# PCI_Express.net
KiCad netlist of a schematic drawn in Altium Designer
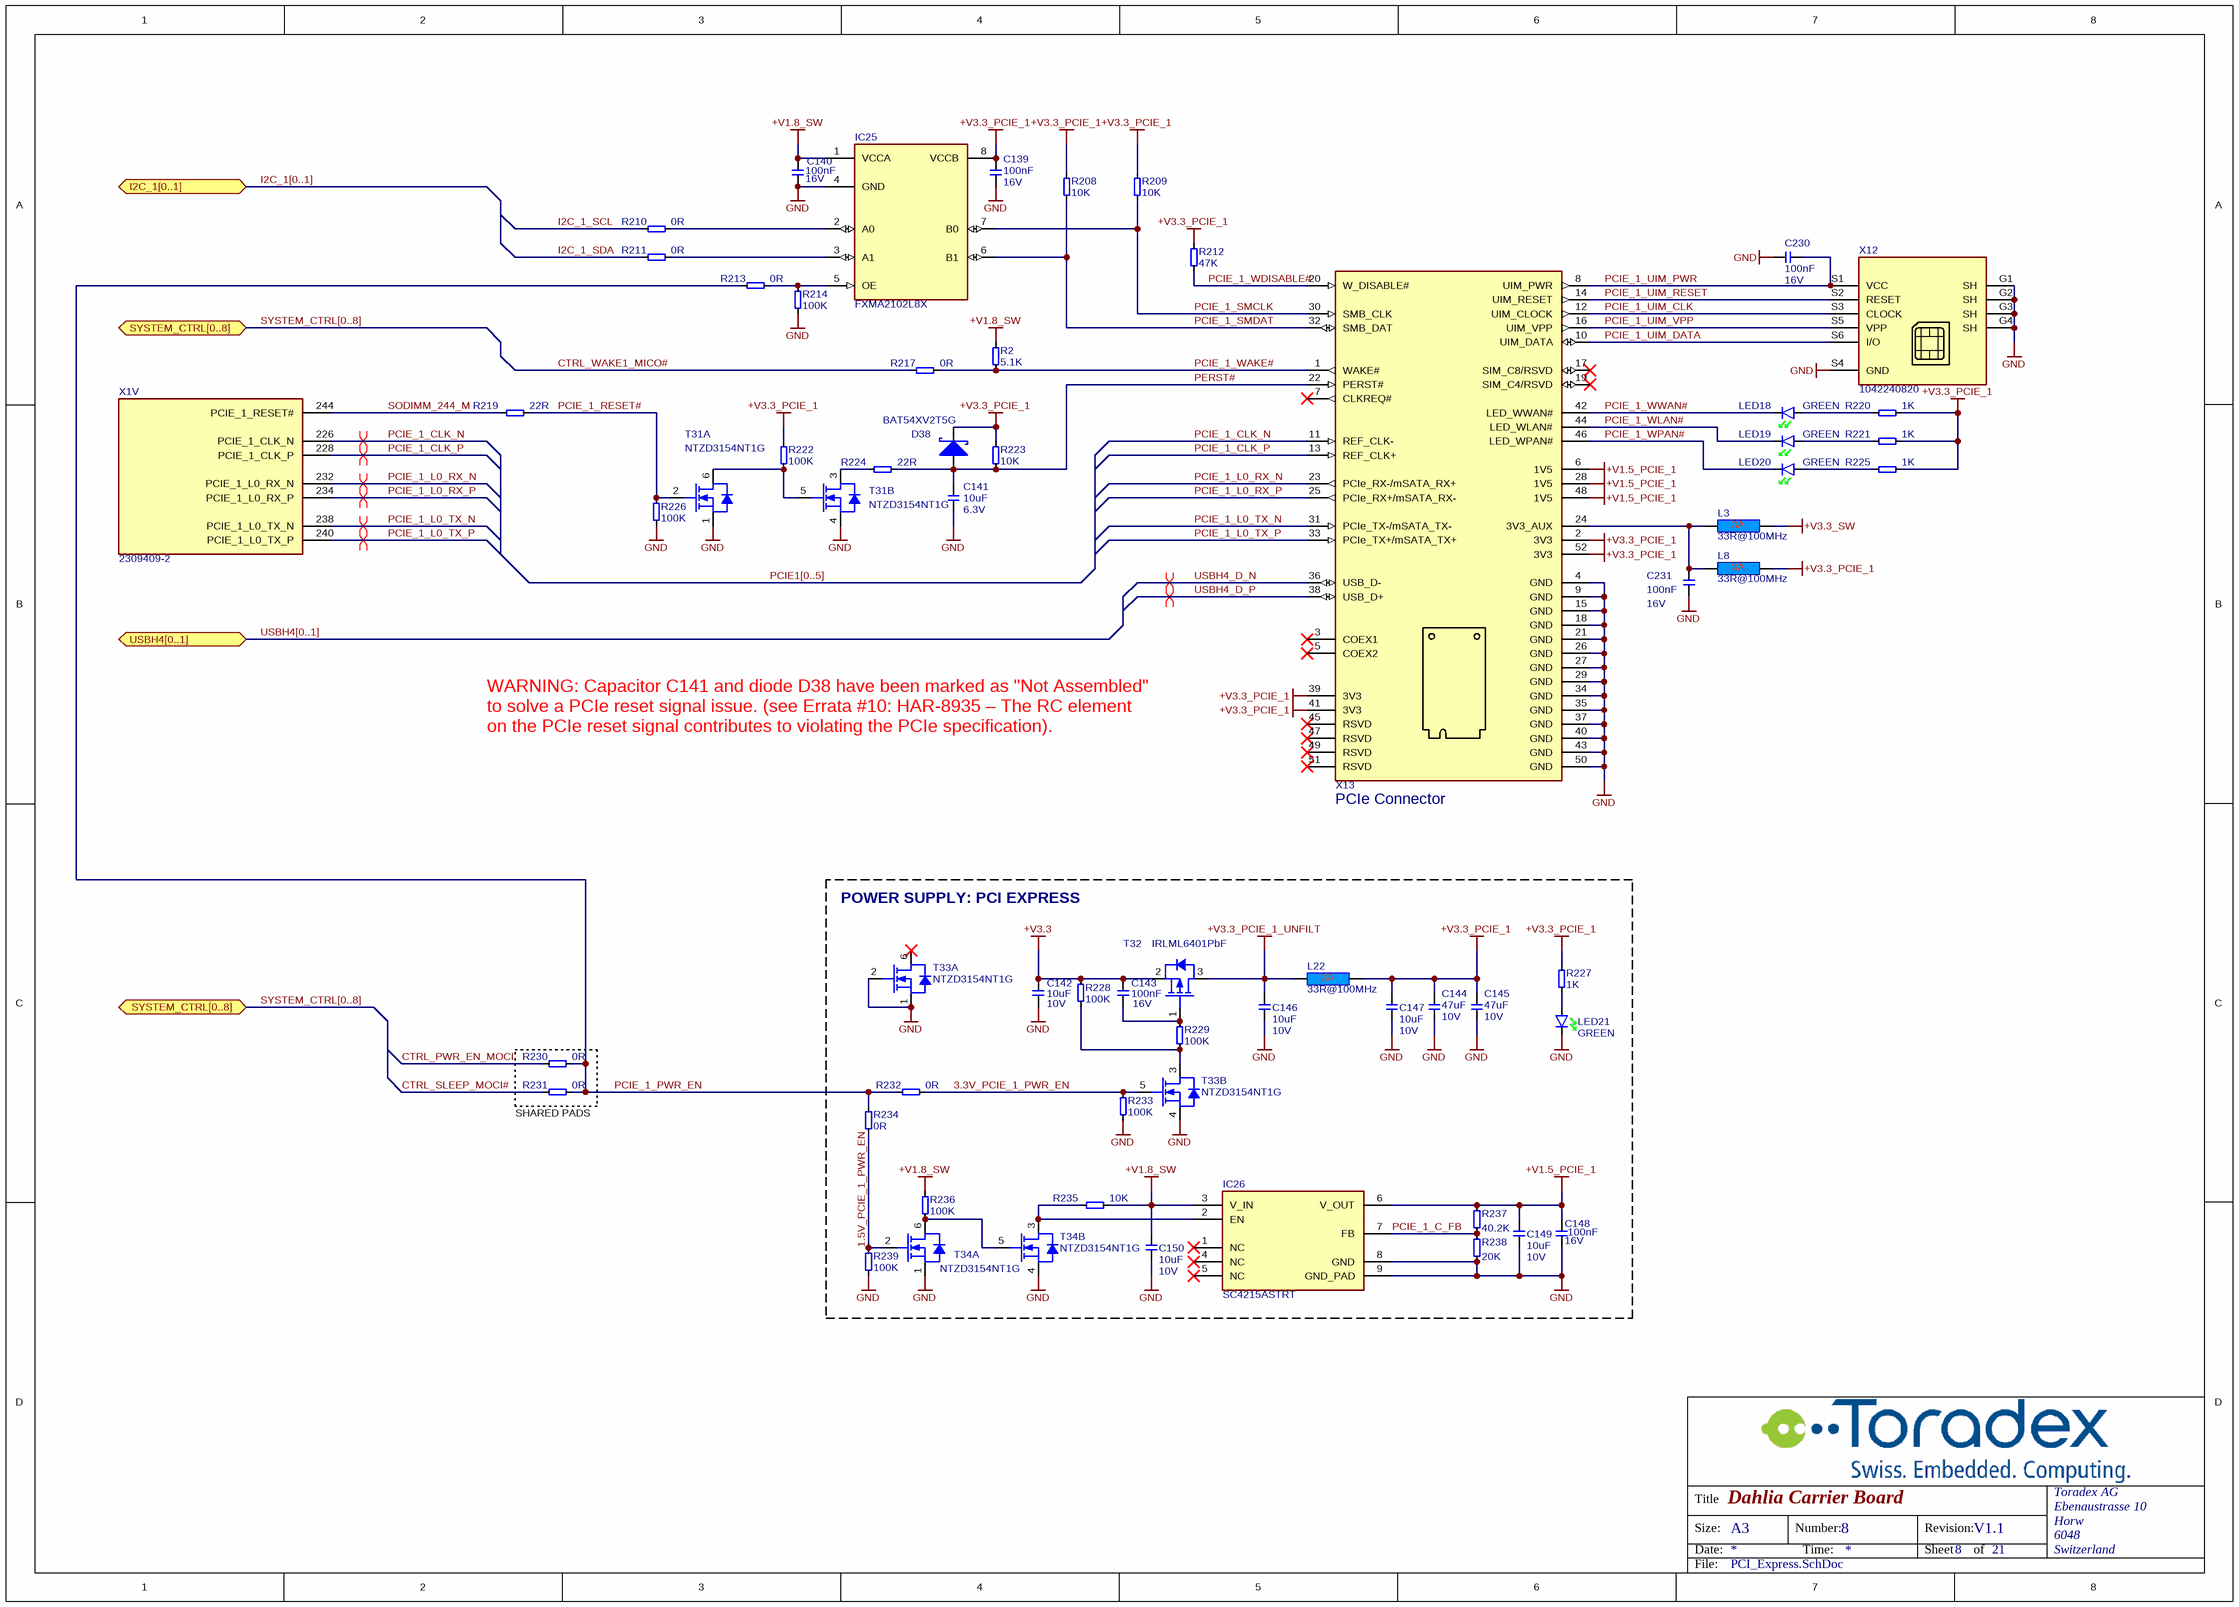
[diagram p0: PCI_Express.SchDoc]

(export (version "E")
  (design (tool "Eeschema 10.0.6"))
  (components
    (comp (ref "C139")
      (value "100nF")
      (footprint "CAPC1005X60N")
      (description "Capacitor Ceramic X7R 100nF 16V 10% 0402")
      (fields (field (name "TOLERANCE") "10%") (field (name "RATING") "16V"))
      (libsource (lib "Dahlia Carrier Board") (part "C-X7R-100nF-16V-10%-0402"))
    )
    (comp (ref "C140")
      (value "100nF")
      (footprint "CAPC1005X60N")
      (description "Capacitor Ceramic X7R 100nF 16V 10% 0402")
      (fields (field (name "TOLERANCE") "10%") (field (name "RATING") "16V"))
      (libsource (lib "Dahlia Carrier Board") (part "C-X7R-100nF-16V-10%-0402"))
    )
    (comp (ref "C141")
      (value "10uF")
      (footprint "CAPC1005X60N")
      (description "Capacitor Ceramic X5R 10uF 6.3V 20% 0402")
      (fields (field (name "TOLERANCE") "20%") (field (name "RATING") "6.3V"))
      (libsource (lib "Dahlia Carrier Board") (part "C-X5R-10u-6.3V-20%-0402"))
    )
    (comp (ref "C142")
      (value "10uF")
      (footprint "T_CAPC0603X33N")
      (description "Capacitor Ceramic X5R 10uF 10V 20% 0603")
      (fields (field (name "TOLERANCE") "20%") (field (name "RATING") "10V"))
      (libsource (lib "Dahlia Carrier Board") (part "C-X5R-10uF-10V-20%-0603"))
    )
    (comp (ref "C143")
      (value "100nF")
      (footprint "CAPC1005X60N")
      (description "Capacitor Ceramic X7R 100nF 16V 10% 0402")
      (fields (field (name "TOLERANCE") "10%") (field (name "RATING") "16V"))
      (libsource (lib "Dahlia Carrier Board") (part "C-X7R-100nF-16V-10%-0402"))
    )
    (comp (ref "C144")
      (value "47uF")
      (footprint "T_CAPC0805X125N")
      (description "Capacitor Ceramic X5R 47uF 10V 20% 0805")
      (fields (field (name "TOLERANCE") "20%") (field (name "RATING") "10V"))
      (libsource (lib "Dahlia Carrier Board") (part "C-X5R-47uF-10V-20%-0805"))
    )
    (comp (ref "C145")
      (value "47uF")
      (footprint "T_CAPC0805X125N")
      (description "Capacitor Ceramic X5R 47uF 10V 20% 0805")
      (fields (field (name "TOLERANCE") "20%") (field (name "RATING") "10V"))
      (libsource (lib "Dahlia Carrier Board") (part "C-X5R-47uF-10V-20%-0805"))
    )
    (comp (ref "C146")
      (value "10uF")
      (footprint "T_CAPC0603X33N")
      (description "Capacitor Ceramic X5R 10uF 10V 20% 0603")
      (fields (field (name "TOLERANCE") "20%") (field (name "RATING") "10V"))
      (libsource (lib "Dahlia Carrier Board") (part "C-X5R-10uF-10V-20%-0603"))
    )
    (comp (ref "C147")
      (value "10uF")
      (footprint "T_CAPC0603X33N")
      (description "Capacitor Ceramic X5R 10uF 10V 20% 0603")
      (fields (field (name "TOLERANCE") "20%") (field (name "RATING") "10V"))
      (libsource (lib "Dahlia Carrier Board") (part "C-X5R-10uF-10V-20%-0603"))
    )
    (comp (ref "C148")
      (value "100nF")
      (footprint "CAPC1005X60N")
      (description "Capacitor Ceramic X7R 100nF 16V 10% 0402")
      (fields (field (name "TOLERANCE") "10%") (field (name "RATING") "16V"))
      (libsource (lib "Dahlia Carrier Board") (part "C-X7R-100nF-16V-10%-0402"))
    )
    (comp (ref "C149")
      (value "10uF")
      (footprint "T_CAPC0603X33N")
      (description "Capacitor Ceramic X5R 10uF 10V 20% 0603")
      (fields (field (name "TOLERANCE") "20%") (field (name "RATING") "10V"))
      (libsource (lib "Dahlia Carrier Board") (part "C-X5R-10uF-10V-20%-0603"))
    )
    (comp (ref "C150")
      (value "10uF")
      (footprint "T_CAPC0603X33N")
      (description "Capacitor Ceramic X5R 10uF 10V 20% 0603")
      (fields (field (name "TOLERANCE") "20%") (field (name "RATING") "10V"))
      (libsource (lib "Dahlia Carrier Board") (part "C-X5R-10uF-10V-20%-0603"))
    )
    (comp (ref "C230")
      (value "100nF")
      (footprint "CAPC1005X60N")
      (description "Capacitor Ceramic X7R 100nF 16V 10% 0402")
      (fields (field (name "TOLERANCE") "10%") (field (name "RATING") "16V"))
      (libsource (lib "Dahlia Carrier Board") (part "C-X7R-100nF-16V-10%-0402"))
    )
    (comp (ref "C231")
      (value "100nF")
      (footprint "CAPC1005X60N")
      (description "Capacitor Ceramic X7R 100nF 16V 10% 0402")
      (fields (field (name "TOLERANCE") "10%") (field (name "RATING") "16V"))
      (libsource (lib "Dahlia Carrier Board") (part "C-X7R-100nF-16V-10%-0402"))
    )
    (comp (ref "D38")
      (value "BAT54XV2T5G")
      (footprint "SOD-523")
      (description "Schottky Barrier Rectifier")
      (fields (field (name "MANUFACTURER PART NO.") "BAT54XV2T5G"))
      (libsource (lib "Dahlia Carrier Board") (part "D-BAT54-SOD523"))
    )
    (comp (ref "IC25")
      (value "FXMA2102L8X")
      (footprint "IC-MicroPak50P160X2160X55-8N")
      (description "Voltage Level Translator for I2C Applications")
      (fields (field (name "MANUFACTURER PART NO.") "FXMA2102L8X"))
      (libsource (lib "Dahlia Carrier Board") (part "IC-ONsemi-FXMA2102L8X"))
    )
    (comp (ref "IC26")
      (value "IC-Semtech-SC4215A")
      (footprint "IC-SOIC127P650X175_HS-8N")
      (description "LDO TO 2A")
      (fields (field (name "MANUFACTURER PART NO.") "SC4215ASTRT"))
      (libsource (lib "Dahlia Carrier Board") (part "IC-Semtech-SC4215A"))
    )
    (comp (ref "L3")
      (value "33R@100MHz")
      (footprint "INDC1608X95N")
      (description "33R@100MHz 3A EMI FILTER")
      (fields (field (name "TOLERANCE") "25%"))
      (libsource (lib "Dahlia Carrier Board") (part "L-33R@100MHz-3A-25%-0603"))
    )
    (comp (ref "L8")
      (value "33R@100MHz")
      (footprint "INDC1608X95N")
      (description "33R@100MHz 3A EMI FILTER")
      (fields (field (name "TOLERANCE") "25%"))
      (libsource (lib "Dahlia Carrier Board") (part "L-33R@100MHz-3A-25%-0603"))
    )
    (comp (ref "L22")
      (value "33R@100MHz")
      (footprint "INDC1608X95N")
      (description "33R@100MHz 3A EMI FILTER")
      (fields (field (name "TOLERANCE") "25%"))
      (libsource (lib "Dahlia Carrier Board") (part "L-33R@100MHz-3A-25%-0603"))
    )
    (comp (ref "LED18")
      (value "LTST-C190GKT")
      (footprint "T_Liteon_LTST-C190GKT")
      (description "LED green Lite-ON LTST-C190GKT")
      (fields (field (name "COLOR") "GREEN"))
      (libsource (lib "Dahlia Carrier Board") (part "LED-LiteOn-LTST-C190GKT"))
    )
    (comp (ref "LED19")
      (value "LTST-C190GKT")
      (footprint "T_Liteon_LTST-C190GKT")
      (description "LED green Lite-ON LTST-C190GKT")
      (fields (field (name "COLOR") "GREEN"))
      (libsource (lib "Dahlia Carrier Board") (part "LED-LiteOn-LTST-C190GKT"))
    )
    (comp (ref "LED20")
      (value "LTST-C190GKT")
      (footprint "T_Liteon_LTST-C190GKT")
      (description "LED green Lite-ON LTST-C190GKT")
      (fields (field (name "COLOR") "GREEN"))
      (libsource (lib "Dahlia Carrier Board") (part "LED-LiteOn-LTST-C190GKT"))
    )
    (comp (ref "LED21")
      (value "LTST-C190GKT")
      (footprint "T_Liteon_LTST-C190GKT")
      (description "LED green Lite-ON LTST-C190GKT")
      (fields (field (name "COLOR") "GREEN"))
      (libsource (lib "Dahlia Carrier Board") (part "LED-LiteOn-LTST-C190GKT"))
    )
    (comp (ref "R2")
      (value "5.1K")
      (footprint "T_RESC0603X30N")
      (description "Resistor 5.1 Kohm 63mW 1% 0603")
      (fields (field (name "TOLERANCE") "1%"))
      (libsource (lib "Dahlia Carrier Board") (part "R-5.1K-63mW-1%-0603"))
    )
    (comp (ref "R208")
      (value "10K")
      (footprint "RESC1005X40N")
      (description "Resistor 10 Kohm 63mW 5% 0402")
      (fields (field (name "TOLERANCE") "5%"))
      (libsource (lib "Dahlia Carrier Board") (part "R-10K-63mW-5%-0402"))
    )
    (comp (ref "R209")
      (value "10K")
      (footprint "RESC1005X40N")
      (description "Resistor 10 Kohm 63mW 5% 0402")
      (fields (field (name "TOLERANCE") "5%"))
      (libsource (lib "Dahlia Carrier Board") (part "R-10K-63mW-5%-0402"))
    )
    (comp (ref "R210")
      (value "0R")
      (footprint "T_RESC0603X30N")
      (description "Resistor 0 ohm 63mW 1% 0603")
      (fields (field (name "TOLERANCE") "1%"))
      (libsource (lib "Dahlia Carrier Board") (part "R-0R-63mW-1%-0603"))
    )
    (comp (ref "R211")
      (value "0R")
      (footprint "T_RESC0603X30N")
      (description "Resistor 0 ohm 63mW 1% 0603")
      (fields (field (name "TOLERANCE") "1%"))
      (libsource (lib "Dahlia Carrier Board") (part "R-0R-63mW-1%-0603"))
    )
    (comp (ref "R212")
      (value "47K")
      (footprint "RESC1005X40N")
      (description "Resistor 47 Kohm 63mW 1% 0402")
      (fields (field (name "TOLERANCE") "1%"))
      (libsource (lib "Dahlia Carrier Board") (part "R-47K-63mW-1%-0402"))
    )
    (comp (ref "R213")
      (value "0R")
      (footprint "T_RESC0603X30N")
      (description "Resistor 0 ohm 63mW 1% 0603")
      (fields (field (name "TOLERANCE") "1%"))
      (libsource (lib "Dahlia Carrier Board") (part "R-0R-63mW-1%-0603"))
    )
    (comp (ref "R214")
      (value "100K")
      (footprint "RESC1005X40N")
      (description "Resistor 100 Kohm 63mW 5% 0402")
      (fields (field (name "TOLERANCE") "5%"))
      (libsource (lib "Dahlia Carrier Board") (part "R-100K-63mW-5%-0402"))
    )
    (comp (ref "R217")
      (value "0R")
      (footprint "T_RESC0603X30N")
      (description "Resistor 0 ohm 63mW 1% 0603")
      (fields (field (name "TOLERANCE") "1%"))
      (libsource (lib "Dahlia Carrier Board") (part "R-0R-63mW-1%-0603"))
    )
    (comp (ref "R219")
      (value "22R")
      (footprint "RESC1005X40N")
      (description "Resistor 22 ohm 63mW 5% 0402")
      (fields (field (name "TOLERANCE") "5%"))
      (libsource (lib "Dahlia Carrier Board") (part "R-22R-63mW-5%-0402"))
    )
    (comp (ref "R220")
      (value "1K")
      (footprint "RESC1005X40N")
      (description "Resistor 1 Kohm 63mW 5% 0402")
      (fields (field (name "TOLERANCE") "5%"))
      (libsource (lib "Dahlia Carrier Board") (part "R-1K-63mW-5%-0402"))
    )
    (comp (ref "R221")
      (value "1K")
      (footprint "RESC1005X40N")
      (description "Resistor 1 Kohm 63mW 5% 0402")
      (fields (field (name "TOLERANCE") "5%"))
      (libsource (lib "Dahlia Carrier Board") (part "R-1K-63mW-5%-0402"))
    )
    (comp (ref "R222")
      (value "100K")
      (footprint "RESC1005X40N")
      (description "Resistor 100 Kohm 63mW 5% 0402")
      (fields (field (name "TOLERANCE") "5%"))
      (libsource (lib "Dahlia Carrier Board") (part "R-100K-63mW-5%-0402"))
    )
    (comp (ref "R223")
      (value "10K")
      (footprint "RESC1005X40N")
      (description "Resistor 10 Kohm 63mW 5% 0402")
      (fields (field (name "TOLERANCE") "5%"))
      (libsource (lib "Dahlia Carrier Board") (part "R-10K-63mW-5%-0402"))
    )
    (comp (ref "R224")
      (value "22R")
      (footprint "RESC1005X40N")
      (description "Resistor 22 ohm 63mW 5% 0402")
      (fields (field (name "TOLERANCE") "5%"))
      (libsource (lib "Dahlia Carrier Board") (part "R-22R-63mW-5%-0402"))
    )
    (comp (ref "R225")
      (value "1K")
      (footprint "RESC1005X40N")
      (description "Resistor 1 Kohm 63mW 5% 0402")
      (fields (field (name "TOLERANCE") "5%"))
      (libsource (lib "Dahlia Carrier Board") (part "R-1K-63mW-5%-0402"))
    )
    (comp (ref "R226")
      (value "100K")
      (footprint "RESC1005X40N")
      (description "Resistor 100 Kohm 63mW 5% 0402")
      (fields (field (name "TOLERANCE") "5%"))
      (libsource (lib "Dahlia Carrier Board") (part "R-100K-63mW-5%-0402"))
    )
    (comp (ref "R227")
      (value "1K")
      (footprint "RESC1005X40N")
      (description "Resistor 1 Kohm 63mW 5% 0402")
      (fields (field (name "TOLERANCE") "5%"))
      (libsource (lib "Dahlia Carrier Board") (part "R-1K-63mW-5%-0402"))
    )
    (comp (ref "R228")
      (value "100K")
      (footprint "RESC1005X40N")
      (description "Resistor 100 Kohm 63mW 5% 0402")
      (fields (field (name "TOLERANCE") "5%"))
      (libsource (lib "Dahlia Carrier Board") (part "R-100K-63mW-5%-0402"))
    )
    (comp (ref "R229")
      (value "100K")
      (footprint "RESC1005X40N")
      (description "Resistor 100 Kohm 63mW 5% 0402")
      (fields (field (name "TOLERANCE") "5%"))
      (libsource (lib "Dahlia Carrier Board") (part "R-100K-63mW-5%-0402"))
    )
    (comp (ref "R230")
      (value "0R")
      (footprint "T_RESC0603X30N")
      (description "Resistor 0 ohm 63mW 1% 0603")
      (fields (field (name "TOLERANCE") "1%"))
      (libsource (lib "Dahlia Carrier Board") (part "R-0R-63mW-1%-0603"))
    )
    (comp (ref "R231")
      (value "0R")
      (footprint "T_RESC0603X30N")
      (description "Resistor 0 ohm 63mW 1% 0603")
      (fields (field (name "TOLERANCE") "1%"))
      (libsource (lib "Dahlia Carrier Board") (part "R-0R-63mW-1%-0603"))
    )
    (comp (ref "R232")
      (value "0R")
      (footprint "T_RESC0603X30N")
      (description "Resistor 0 ohm 63mW 1% 0603")
      (fields (field (name "TOLERANCE") "1%"))
      (libsource (lib "Dahlia Carrier Board") (part "R-0R-63mW-1%-0603"))
    )
    (comp (ref "R233")
      (value "100K")
      (footprint "RESC1005X40N")
      (description "Resistor 100 Kohm 63mW 5% 0402")
      (fields (field (name "TOLERANCE") "5%"))
      (libsource (lib "Dahlia Carrier Board") (part "R-100K-63mW-5%-0402"))
    )
    (comp (ref "R234")
      (value "0R")
      (footprint "T_RESC0603X30N")
      (description "Resistor 0 ohm 63mW 1% 0603")
      (fields (field (name "TOLERANCE") "1%"))
      (libsource (lib "Dahlia Carrier Board") (part "R-0R-63mW-1%-0603"))
    )
    (comp (ref "R235")
      (value "10K")
      (footprint "RESC1005X40N")
      (description "Resistor 10 Kohm 63mW 5% 0402")
      (fields (field (name "TOLERANCE") "5%"))
      (libsource (lib "Dahlia Carrier Board") (part "R-10K-63mW-5%-0402"))
    )
    (comp (ref "R236")
      (value "100K")
      (footprint "RESC1005X40N")
      (description "Resistor 100 Kohm 63mW 5% 0402")
      (fields (field (name "TOLERANCE") "5%"))
      (libsource (lib "Dahlia Carrier Board") (part "R-100K-63mW-5%-0402"))
    )
    (comp (ref "R237")
      (value "40.2K")
      (footprint "RESC1005X40N")
      (description "Resistor 40.2 Kohm 63mW 1% 0402")
      (fields (field (name "TOLERANCE") "1%"))
      (libsource (lib "Dahlia Carrier Board") (part "R-40.2KR-63mW-1%-0402"))
    )
    (comp (ref "R238")
      (value "20K")
      (footprint "RESC1005X40N")
      (description "Resistor 20 Kohm 63mW 1% 0402")
      (fields (field (name "TOLERANCE") "1%"))
      (libsource (lib "Dahlia Carrier Board") (part "R-20KR-63mW-1%-0402"))
    )
    (comp (ref "R239")
      (value "100K")
      (footprint "RESC1005X40N")
      (description "Resistor 100 Kohm 63mW 5% 0402")
      (fields (field (name "TOLERANCE") "5%"))
      (libsource (lib "Dahlia Carrier Board") (part "R-100K-63mW-5%-0402"))
    )
    (comp (ref "T31")
      (value "T-ONSemi-NTZD3154NT1G")
      (footprint "SOTFL50P160X60-6N")
      (description "Dual N-Channel 20V (D-S)  MOSFET")
      (fields (field (name "MANUFACTURER PART NO.") "NTZD3154NT1G"))
      (libsource (lib "Dahlia Carrier Board") (part "T-ONSemi-NTZD3154NT1G"))
    )
    (comp (ref "T32")
      (value "IRLML6401PbF")
      (footprint "SOT95P237X112-3N")
      (description "p-channel MOSFET, IRLML6401PbF")
      (libsource (lib "Dahlia Carrier Board") (part "T-IR-IRLML6401PbF-SOT-23"))
    )
    (comp (ref "T33")
      (value "T-ONSemi-NTZD3154NT1G")
      (footprint "SOTFL50P160X60-6N")
      (description "Dual N-Channel 20V (D-S)  MOSFET")
      (fields (field (name "MANUFACTURER PART NO.") "NTZD3154NT1G"))
      (libsource (lib "Dahlia Carrier Board") (part "T-ONSemi-NTZD3154NT1G"))
    )
    (comp (ref "T34")
      (value "T-ONSemi-NTZD3154NT1G")
      (footprint "SOTFL50P160X60-6N")
      (description "Dual N-Channel 20V (D-S)  MOSFET")
      (fields (field (name "MANUFACTURER PART NO.") "NTZD3154NT1G"))
      (libsource (lib "Dahlia Carrier Board") (part "T-ONSemi-NTZD3154NT1G"))
    )
    (comp (ref "X1")
      (value "2309409-2")
      (footprint "CON-TE-2309409-2-SOLDERABLE-STANDOFFS")
      (description "DDR4 SODIMM Socket, 260 pins, 5.2mm(H), 0.5mm Pitch")
      (libsource (lib "Dahlia Carrier Board") (part "CON-TE-2309409-2"))
    )
    (comp (ref "X12")
      (value "1042240820")
      (footprint "T_Molex_1042240820")
      (description "6 Contacts Nano Sim Card Holder")
      (fields (field (name "MANUFACTURER PART NO.") "1042240820"))
      (libsource (lib "Dahlia Carrier Board") (part "CON-Molex-1042240820"))
    )
    (comp (ref "X13")
      (value "67910-5700")
      (footprint "CON-Molex-67910-5700-Half/Full")
      (description "PCIe_Mini Card Holder")
      (libsource (lib "Dahlia Carrier Board") (part "CON-Molex-67910-5700"))
    )
  )
  (nets
    (net (code "20") (name "+V1.5_PCIE_1") (class "Default")
      (node (ref "C148") (pin "2") (pinfunction "2_2") (pintype "passive"))
      (node (ref "C149") (pin "2") (pinfunction "2_2") (pintype "passive"))
      (node (ref "IC26") (pin "6") (pinfunction "V_OUT_6") (pintype "passive"))
      (node (ref "R237") (pin "2") (pinfunction "2_2") (pintype "passive"))
      (node (ref "X13") (pin "28") (pinfunction "1V5_28") (pintype "power_in"))
      (node (ref "X13") (pin "48") (pinfunction "1V5_48") (pintype "power_in"))
      (node (ref "X13") (pin "6") (pinfunction "1V5_6") (pintype "power_in"))
    )
    (net (code "21") (name "+V1.8_SW") (class "Default")
      (node (ref "C140") (pin "2") (pinfunction "2_2") (pintype "passive"))
      (node (ref "C150") (pin "2") (pinfunction "2_2") (pintype "passive"))
      (node (ref "IC25") (pin "1") (pinfunction "VCCA_1") (pintype "power_in"))
      (node (ref "IC26") (pin "3") (pinfunction "V_IN_3") (pintype "passive"))
      (node (ref "R2") (pin "1") (pinfunction "1_1") (pintype "passive"))
      (node (ref "R235") (pin "1") (pinfunction "1_1") (pintype "passive"))
      (node (ref "R236") (pin "2") (pinfunction "2_2") (pintype "passive"))
    )
    (net (code "22") (name "+V3.3") (class "Default")
      (node (ref "C142") (pin "2") (pinfunction "2_2") (pintype "passive"))
      (node (ref "C143") (pin "2") (pinfunction "2_2") (pintype "passive"))
      (node (ref "R228") (pin "2") (pinfunction "2_2") (pintype "passive"))
      (node (ref "T32") (pin "2") (pinfunction "S_2") (pintype "passive"))
    )
    (net (code "23") (name "+V3.3_PCIE_1") (class "Default")
      (node (ref "C139") (pin "2") (pinfunction "2_2") (pintype "passive"))
      (node (ref "C144") (pin "2") (pinfunction "2_2") (pintype "passive"))
      (node (ref "C145") (pin "2") (pinfunction "2_2") (pintype "passive"))
      (node (ref "C147") (pin "2") (pinfunction "2_2") (pintype "passive"))
      (node (ref "D38") (pin "C") (pinfunction "C_C") (pintype "passive"))
      (node (ref "IC25") (pin "8") (pinfunction "VCCB_8") (pintype "power_in"))
      (node (ref "L22") (pin "2") (pinfunction "2_2") (pintype "passive"))
      (node (ref "L8") (pin "2") (pinfunction "2_2") (pintype "passive"))
      (node (ref "R208") (pin "2") (pinfunction "2_2") (pintype "passive"))
      (node (ref "R209") (pin "2") (pinfunction "2_2") (pintype "passive"))
      (node (ref "R212") (pin "2") (pinfunction "2_2") (pintype "passive"))
      (node (ref "R220") (pin "1") (pinfunction "1_1") (pintype "passive"))
      (node (ref "R221") (pin "1") (pinfunction "1_1") (pintype "passive"))
      (node (ref "R222") (pin "2") (pinfunction "2_2") (pintype "passive"))
      (node (ref "R223") (pin "2") (pinfunction "2_2") (pintype "passive"))
      (node (ref "R225") (pin "1") (pinfunction "1_1") (pintype "passive"))
      (node (ref "R227") (pin "2") (pinfunction "2_2") (pintype "passive"))
      (node (ref "X13") (pin "2") (pinfunction "3V3_2") (pintype "power_in"))
      (node (ref "X13") (pin "39") (pinfunction "3V3_39") (pintype "passive"))
      (node (ref "X13") (pin "41") (pinfunction "3V3_41") (pintype "passive"))
      (node (ref "X13") (pin "52") (pinfunction "3V3_52") (pintype "power_in"))
    )
    (net (code "24") (name "+V3.3_PCIE_1_UNFILT") (class "Default")
      (node (ref "C146") (pin "2") (pinfunction "2_2") (pintype "passive"))
      (node (ref "L22") (pin "1") (pinfunction "1_1") (pintype "passive"))
      (node (ref "T32") (pin "3") (pinfunction "D_3") (pintype "passive"))
    )
    (net (code "25") (name "+V3.3_SW") (class "Default")
      (node (ref "L3") (pin "2") (pinfunction "2_2") (pintype "passive"))
    )
    (net (code "26") (name "/1.5V_PCIE_1_PWR_EN") (class "Default")
      (node (ref "R234") (pin "1") (pinfunction "1_1") (pintype "passive"))
      (node (ref "R239") (pin "2") (pinfunction "2_2") (pintype "passive"))
      (node (ref "T34") (pin "2") (pinfunction "G_2") (pintype "passive"))
    )
    (net (code "27") (name "/3.3V_PCIE_1_PWR_EN") (class "Default")
      (node (ref "R232") (pin "2") (pinfunction "2_2") (pintype "passive"))
      (node (ref "R233") (pin "2") (pinfunction "2_2") (pintype "passive"))
      (node (ref "T33") (pin "5") (pinfunction "G_5") (pintype "passive"))
    )
    (net (code "28") (name "/CTRL_PWR_EN_MOCI") (class "Default")
      (node (ref "R230") (pin "1") (pinfunction "1_1") (pintype "passive"))
    )
    (net (code "29") (name "/CTRL_SLEEP_MOCI#") (class "Default")
      (node (ref "R231") (pin "1") (pinfunction "1_1") (pintype "passive"))
    )
    (net (code "30") (name "/CTRL_WAKE1_MICO#") (class "Default")
      (node (ref "R217") (pin "1") (pinfunction "1_1") (pintype "passive"))
    )
    (net (code "32") (name "/I2C_1_SCL") (class "Default")
      (node (ref "R210") (pin "1") (pinfunction "1_1") (pintype "passive"))
    )
    (net (code "33") (name "/I2C_1_SDA") (class "Default")
      (node (ref "R211") (pin "1") (pinfunction "1_1") (pintype "passive"))
    )
    (net (code "35") (name "/PCIE_1_CLK_N") (class "Default")
      (node (ref "X1") (pin "226") (pinfunction "PCIE_1_CLK_N_226") (pintype "passive"))
      (node (ref "X13") (pin "11") (pinfunction "REF_CLK-_11") (pintype "input"))
    )
    (net (code "36") (name "/PCIE_1_CLK_P") (class "Default")
      (node (ref "X1") (pin "228") (pinfunction "PCIE_1_CLK_P_228") (pintype "passive"))
      (node (ref "X13") (pin "13") (pinfunction "REF_CLK+_13") (pintype "input"))
    )
    (net (code "37") (name "/PCIE_1_C_FB") (class "Default")
      (node (ref "IC26") (pin "7") (pinfunction "FB_7") (pintype "passive"))
      (node (ref "R237") (pin "1") (pinfunction "1_1") (pintype "passive"))
      (node (ref "R238") (pin "2") (pinfunction "2_2") (pintype "passive"))
    )
    (net (code "38") (name "/PCIE_1_L0_RX_N") (class "Default")
      (node (ref "X1") (pin "232") (pinfunction "PCIE_1_L0_RX_N_232") (pintype "passive"))
      (node (ref "X13") (pin "23") (pinfunction "PCIe_RX-/mSATA_RX+_23") (pintype "output"))
    )
    (net (code "39") (name "/PCIE_1_L0_RX_P") (class "Default")
      (node (ref "X1") (pin "234") (pinfunction "PCIE_1_L0_RX_P_234") (pintype "passive"))
      (node (ref "X13") (pin "25") (pinfunction "PCIe_RX+/mSATA_RX-_25") (pintype "output"))
    )
    (net (code "40") (name "/PCIE_1_L0_TX_N") (class "Default")
      (node (ref "X1") (pin "238") (pinfunction "PCIE_1_L0_TX_N_238") (pintype "passive"))
      (node (ref "X13") (pin "31") (pinfunction "PCIe_TX-/mSATA_TX-_31") (pintype "input"))
    )
    (net (code "41") (name "/PCIE_1_L0_TX_P") (class "Default")
      (node (ref "X1") (pin "240") (pinfunction "PCIE_1_L0_TX_P_240") (pintype "passive"))
      (node (ref "X13") (pin "33") (pinfunction "PCIe_TX+/mSATA_TX+_33") (pintype "input"))
    )
    (net (code "42") (name "/PCIE_1_PWR_EN") (class "Default")
      (node (ref "R213") (pin "1") (pinfunction "1_1") (pintype "passive"))
      (node (ref "R230") (pin "2") (pinfunction "2_2") (pintype "passive"))
      (node (ref "R231") (pin "2") (pinfunction "2_2") (pintype "passive"))
      (node (ref "R232") (pin "1") (pinfunction "1_1") (pintype "passive"))
      (node (ref "R234") (pin "2") (pinfunction "2_2") (pintype "passive"))
    )
    (net (code "43") (name "/PCIE_1_RESET#") (class "Default")
      (node (ref "R219") (pin "2") (pinfunction "2_2") (pintype "passive"))
      (node (ref "R226") (pin "2") (pinfunction "2_2") (pintype "passive"))
      (node (ref "T31") (pin "2") (pinfunction "G_2") (pintype "passive"))
    )
    (net (code "44") (name "/PCIE_1_SMCLK") (class "Default")
      (node (ref "IC25") (pin "7") (pinfunction "B0_7") (pintype "bidirectional"))
      (node (ref "R209") (pin "1") (pinfunction "1_1") (pintype "passive"))
      (node (ref "X13") (pin "30") (pinfunction "SMB_CLK_30") (pintype "input"))
    )
    (net (code "45") (name "/PCIE_1_SMDAT") (class "Default")
      (node (ref "IC25") (pin "6") (pinfunction "B1_6") (pintype "bidirectional"))
      (node (ref "R208") (pin "1") (pinfunction "1_1") (pintype "passive"))
      (node (ref "X13") (pin "32") (pinfunction "SMB_DAT_32") (pintype "bidirectional"))
    )
    (net (code "46") (name "/PCIE_1_UIM_CLK") (class "Default")
      (node (ref "X12") (pin "S3") (pinfunction "CLOCK_S3") (pintype "passive"))
      (node (ref "X13") (pin "12") (pinfunction "UIM_CLOCK_12") (pintype "output"))
    )
    (net (code "47") (name "/PCIE_1_UIM_DATA") (class "Default")
      (node (ref "X12") (pin "S6") (pinfunction "I/O_S6") (pintype "passive"))
      (node (ref "X13") (pin "10") (pinfunction "UIM_DATA_10") (pintype "bidirectional"))
    )
    (net (code "48") (name "/PCIE_1_UIM_PWR") (class "Default")
      (node (ref "C230") (pin "2") (pinfunction "2_2") (pintype "passive"))
      (node (ref "X12") (pin "S1") (pinfunction "VCC_S1") (pintype "passive"))
      (node (ref "X13") (pin "8") (pinfunction "UIM_PWR_8") (pintype "output"))
    )
    (net (code "49") (name "/PCIE_1_UIM_RESET") (class "Default")
      (node (ref "X12") (pin "S2") (pinfunction "RESET_S2") (pintype "passive"))
      (node (ref "X13") (pin "14") (pinfunction "UIM_RESET_14") (pintype "output"))
    )
    (net (code "50") (name "/PCIE_1_UIM_VPP") (class "Default")
      (node (ref "X12") (pin "S5") (pinfunction "VPP_S5") (pintype "passive"))
      (node (ref "X13") (pin "16") (pinfunction "UIM_VPP_16") (pintype "output"))
    )
    (net (code "51") (name "/PCIE_1_WAKE#") (class "Default")
      (node (ref "R2") (pin "2") (pinfunction "2_2") (pintype "passive"))
      (node (ref "R217") (pin "2") (pinfunction "2_2") (pintype "passive"))
      (node (ref "X13") (pin "1") (pinfunction "WAKE#_1") (pintype "output"))
    )
    (net (code "53") (name "/PCIE_1_WDISABLE#") (class "Default")
      (node (ref "R212") (pin "1") (pinfunction "1_1") (pintype "passive"))
      (node (ref "X13") (pin "20") (pinfunction "W_DISABLE#_20") (pintype "input"))
    )
    (net (code "54") (name "/PCIE_1_WLAN#") (class "Default")
      (node (ref "LED19") (pin "K") (pinfunction "K_K") (pintype "passive"))
      (node (ref "X13") (pin "44") (pinfunction "LED_WLAN#_44") (pintype "open_collector"))
    )
    (net (code "55") (name "/PCIE_1_WPAN#") (class "Default")
      (node (ref "LED20") (pin "K") (pinfunction "K_K") (pintype "passive"))
      (node (ref "X13") (pin "46") (pinfunction "LED_WPAN#_46") (pintype "open_collector"))
    )
    (net (code "56") (name "/PCIE_1_WWAN#") (class "Default")
      (node (ref "LED18") (pin "K") (pinfunction "K_K") (pintype "passive"))
      (node (ref "X13") (pin "42") (pinfunction "LED_WWAN#_42") (pintype "open_collector"))
    )
    (net (code "57") (name "/PERST#") (class "Default")
      (node (ref "C141") (pin "2") (pinfunction "2_2") (pintype "passive"))
      (node (ref "D38") (pin "A") (pinfunction "A_A") (pintype "passive"))
      (node (ref "R223") (pin "1") (pinfunction "1_1") (pintype "passive"))
      (node (ref "R224") (pin "2") (pinfunction "2_2") (pintype "passive"))
      (node (ref "X13") (pin "22") (pinfunction "PERST#_22") (pintype "input"))
    )
    (net (code "60") (name "/SODIMM_244_M") (class "Default")
      (node (ref "R219") (pin "1") (pinfunction "1_1") (pintype "passive"))
      (node (ref "X1") (pin "244") (pinfunction "PCIE_1_RESET#_244") (pintype "passive"))
    )
    (net (code "61") (name "/USBH4_D_N") (class "Default")
      (node (ref "X13") (pin "36") (pinfunction "USB_D-_36") (pintype "bidirectional"))
    )
    (net (code "62") (name "/USBH4_D_P") (class "Default")
      (node (ref "X13") (pin "38") (pinfunction "USB_D+_38") (pintype "bidirectional"))
    )
    (net (code "63") (name "GND") (class "Default")
      (node (ref "C139") (pin "1") (pinfunction "1_1") (pintype "passive"))
      (node (ref "C140") (pin "1") (pinfunction "1_1") (pintype "passive"))
      (node (ref "C141") (pin "1") (pinfunction "1_1") (pintype "passive"))
      (node (ref "C142") (pin "1") (pinfunction "1_1") (pintype "passive"))
      (node (ref "C144") (pin "1") (pinfunction "1_1") (pintype "passive"))
      (node (ref "C145") (pin "1") (pinfunction "1_1") (pintype "passive"))
      (node (ref "C146") (pin "1") (pinfunction "1_1") (pintype "passive"))
      (node (ref "C147") (pin "1") (pinfunction "1_1") (pintype "passive"))
      (node (ref "C148") (pin "1") (pinfunction "1_1") (pintype "passive"))
      (node (ref "C149") (pin "1") (pinfunction "1_1") (pintype "passive"))
      (node (ref "C150") (pin "1") (pinfunction "1_1") (pintype "passive"))
      (node (ref "C230") (pin "1") (pinfunction "1_1") (pintype "passive"))
      (node (ref "C231") (pin "1") (pinfunction "1_1") (pintype "passive"))
      (node (ref "IC25") (pin "4") (pinfunction "GND_4") (pintype "power_in"))
      (node (ref "IC26") (pin "8") (pinfunction "GND_8") (pintype "passive"))
      (node (ref "IC26") (pin "9") (pinfunction "GND_PAD_9") (pintype "passive"))
      (node (ref "LED21") (pin "K") (pinfunction "K_K") (pintype "passive"))
      (node (ref "R214") (pin "1") (pinfunction "1_1") (pintype "passive"))
      (node (ref "R226") (pin "1") (pinfunction "1_1") (pintype "passive"))
      (node (ref "R233") (pin "1") (pinfunction "1_1") (pintype "passive"))
      (node (ref "R238") (pin "1") (pinfunction "1_1") (pintype "passive"))
      (node (ref "R239") (pin "1") (pinfunction "1_1") (pintype "passive"))
      (node (ref "T31") (pin "1") (pinfunction "S_1") (pintype "passive"))
      (node (ref "T31") (pin "4") (pinfunction "S_4") (pintype "passive"))
      (node (ref "T33") (pin "1") (pinfunction "S_1") (pintype "passive"))
      (node (ref "T33") (pin "2") (pinfunction "G_2") (pintype "passive"))
      (node (ref "T33") (pin "4") (pinfunction "S_4") (pintype "passive"))
      (node (ref "T34") (pin "1") (pinfunction "S_1") (pintype "passive"))
      (node (ref "T34") (pin "4") (pinfunction "S_4") (pintype "passive"))
      (node (ref "X12") (pin "G1") (pinfunction "SH_G1") (pintype "passive"))
      (node (ref "X12") (pin "G2") (pinfunction "SH_G2") (pintype "passive"))
      (node (ref "X12") (pin "G3") (pinfunction "SH_G3") (pintype "passive"))
      (node (ref "X12") (pin "G4") (pinfunction "SH_G4") (pintype "passive"))
      (node (ref "X12") (pin "S4") (pinfunction "GND_S4") (pintype "passive"))
      (node (ref "X13") (pin "15") (pinfunction "GND_15") (pintype "power_in"))
      (node (ref "X13") (pin "18") (pinfunction "GND_18") (pintype "power_in"))
      (node (ref "X13") (pin "21") (pinfunction "GND_21") (pintype "power_in"))
      (node (ref "X13") (pin "26") (pinfunction "GND_26") (pintype "power_in"))
      (node (ref "X13") (pin "27") (pinfunction "GND_27") (pintype "power_in"))
      (node (ref "X13") (pin "29") (pinfunction "GND_29") (pintype "power_in"))
      (node (ref "X13") (pin "34") (pinfunction "GND_34") (pintype "power_in"))
      (node (ref "X13") (pin "35") (pinfunction "GND_35") (pintype "power_in"))
      (node (ref "X13") (pin "37") (pinfunction "GND_37") (pintype "power_in"))
      (node (ref "X13") (pin "4") (pinfunction "GND_4") (pintype "power_in"))
      (node (ref "X13") (pin "40") (pinfunction "GND_40") (pintype "power_in"))
      (node (ref "X13") (pin "43") (pinfunction "GND_43") (pintype "power_in"))
      (node (ref "X13") (pin "50") (pinfunction "GND_50") (pintype "power_in"))
      (node (ref "X13") (pin "9") (pinfunction "GND_9") (pintype "power_in"))
    )
    (net (code "64") (name "Net-(IC25-A0)") (class "Default")
      (node (ref "IC25") (pin "2") (pinfunction "A0_2") (pintype "bidirectional"))
      (node (ref "R210") (pin "2") (pinfunction "2_2") (pintype "passive"))
    )
    (net (code "65") (name "Net-(IC25-A1)") (class "Default")
      (node (ref "IC25") (pin "3") (pinfunction "A1_3") (pintype "bidirectional"))
      (node (ref "R211") (pin "2") (pinfunction "2_2") (pintype "passive"))
    )
    (net (code "66") (name "Net-(IC25-OE)") (class "Default")
      (node (ref "IC25") (pin "5") (pinfunction "OE_5") (pintype "input"))
      (node (ref "R213") (pin "2") (pinfunction "2_2") (pintype "passive"))
      (node (ref "R214") (pin "2") (pinfunction "2_2") (pintype "passive"))
    )
    (net (code "67") (name "Net-(IC26-EN)") (class "Default")
      (node (ref "IC26") (pin "2") (pinfunction "EN_2") (pintype "passive"))
      (node (ref "R235") (pin "2") (pinfunction "2_2") (pintype "passive"))
      (node (ref "T34") (pin "3") (pinfunction "D_3") (pintype "passive"))
    )
    (net (code "68") (name "Net-(LED18-PadA)") (class "Default")
      (node (ref "LED18") (pin "A") (pinfunction "A_A") (pintype "passive"))
      (node (ref "R220") (pin "2") (pinfunction "2_2") (pintype "passive"))
    )
    (net (code "69") (name "Net-(LED19-PadA)") (class "Default")
      (node (ref "LED19") (pin "A") (pinfunction "A_A") (pintype "passive"))
      (node (ref "R221") (pin "2") (pinfunction "2_2") (pintype "passive"))
    )
    (net (code "70") (name "Net-(LED20-PadA)") (class "Default")
      (node (ref "LED20") (pin "A") (pinfunction "A_A") (pintype "passive"))
      (node (ref "R225") (pin "2") (pinfunction "2_2") (pintype "passive"))
    )
    (net (code "71") (name "Net-(LED21-PadA)") (class "Default")
      (node (ref "LED21") (pin "A") (pinfunction "A_A") (pintype "passive"))
      (node (ref "R227") (pin "1") (pinfunction "1_1") (pintype "passive"))
    )
    (net (code "72") (name "Net-(T31A-D)") (class "Default")
      (node (ref "R222") (pin "1") (pinfunction "1_1") (pintype "passive"))
      (node (ref "T31") (pin "5") (pinfunction "G_5") (pintype "passive"))
      (node (ref "T31") (pin "6") (pinfunction "D_6") (pintype "passive"))
    )
    (net (code "73") (name "Net-(T31B-D)") (class "Default")
      (node (ref "R224") (pin "1") (pinfunction "1_1") (pintype "passive"))
      (node (ref "T31") (pin "3") (pinfunction "D_3") (pintype "passive"))
    )
    (net (code "74") (name "Net-(T32-G)") (class "Default")
      (node (ref "C143") (pin "1") (pinfunction "1_1") (pintype "passive"))
      (node (ref "R229") (pin "2") (pinfunction "2_2") (pintype "passive"))
      (node (ref "T32") (pin "1") (pinfunction "G_1") (pintype "passive"))
    )
    (net (code "75") (name "Net-(T33B-D)") (class "Default")
      (node (ref "R228") (pin "1") (pinfunction "1_1") (pintype "passive"))
      (node (ref "R229") (pin "1") (pinfunction "1_1") (pintype "passive"))
      (node (ref "T33") (pin "3") (pinfunction "D_3") (pintype "passive"))
    )
    (net (code "76") (name "Net-(T34A-D)") (class "Default")
      (node (ref "R236") (pin "1") (pinfunction "1_1") (pintype "passive"))
      (node (ref "T34") (pin "5") (pinfunction "G_5") (pintype "passive"))
      (node (ref "T34") (pin "6") (pinfunction "D_6") (pintype "passive"))
    )
    (net (code "77") (name "Net-(X13-3V3_AUX)") (class "Default")
      (node (ref "C231") (pin "2") (pinfunction "2_2") (pintype "passive"))
      (node (ref "L3") (pin "1") (pinfunction "1_1") (pintype "passive"))
      (node (ref "L8") (pin "1") (pinfunction "1_1") (pintype "passive"))
      (node (ref "X13") (pin "24") (pinfunction "3V3_AUX_24") (pintype "power_in"))
    )
    (net (code "78") (name "unconnected-(IC26-NC-Pad1)") (class "Default")
      (node (ref "IC26") (pin "1") (pinfunction "NC_1") (pintype "passive+no_connect"))
    )
    (net (code "79") (name "unconnected-(IC26-NC-Pad4)") (class "Default")
      (node (ref "IC26") (pin "4") (pinfunction "NC_4") (pintype "passive+no_connect"))
    )
    (net (code "80") (name "unconnected-(IC26-NC-Pad5)") (class "Default")
      (node (ref "IC26") (pin "5") (pinfunction "NC_5") (pintype "passive+no_connect"))
    )
    (net (code "81") (name "unconnected-(T33A-D-Pad6)") (class "Default")
      (node (ref "T33") (pin "6") (pinfunction "D_6") (pintype "passive+no_connect"))
    )
    (net (code "82") (name "unconnected-(X13-CLKREQ#-Pad7)") (class "Default")
      (node (ref "X13") (pin "7") (pinfunction "CLKREQ#_7") (pintype "output+no_connect"))
    )
    (net (code "83") (name "unconnected-(X13-COEX1-Pad3)") (class "Default")
      (node (ref "X13") (pin "3") (pinfunction "COEX1_3") (pintype "passive+no_connect"))
    )
    (net (code "84") (name "unconnected-(X13-COEX2-Pad5)") (class "Default")
      (node (ref "X13") (pin "5") (pinfunction "COEX2_5") (pintype "passive+no_connect"))
    )
    (net (code "85") (name "unconnected-(X13-RSVD-Pad45)") (class "Default")
      (node (ref "X13") (pin "45") (pinfunction "RSVD_45") (pintype "passive+no_connect"))
    )
    (net (code "86") (name "unconnected-(X13-RSVD-Pad47)") (class "Default")
      (node (ref "X13") (pin "47") (pinfunction "RSVD_47") (pintype "passive+no_connect"))
    )
    (net (code "87") (name "unconnected-(X13-RSVD-Pad49)") (class "Default")
      (node (ref "X13") (pin "49") (pinfunction "RSVD_49") (pintype "passive+no_connect"))
    )
    (net (code "88") (name "unconnected-(X13-RSVD-Pad51)") (class "Default")
      (node (ref "X13") (pin "51") (pinfunction "RSVD_51") (pintype "passive+no_connect"))
    )
    (net (code "89") (name "unconnected-(X13-SIM_C4{slash}RSVD-Pad19)") (class "Default")
      (node (ref "X13") (pin "19") (pinfunction "SIM_C4/RSVD_19") (pintype "bidirectional+no_connect"))
    )
    (net (code "90") (name "unconnected-(X13-SIM_C8{slash}RSVD-Pad17)") (class "Default")
      (node (ref "X13") (pin "17") (pinfunction "SIM_C8/RSVD_17") (pintype "bidirectional+no_connect"))
    )
  )
)
